# Bpod_Serial_Shield_r3.net
KiCad netlist of a schematic drawn in EAGLE
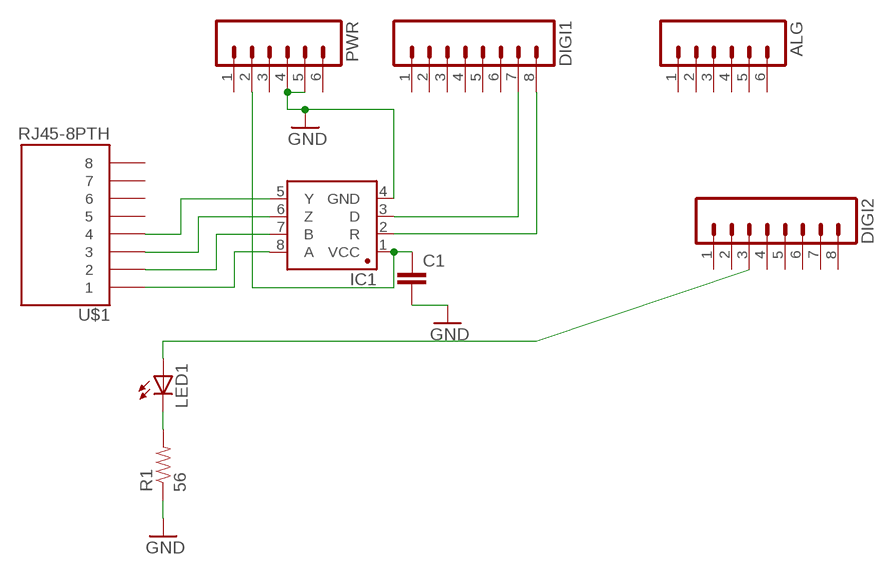
[diagram p0: schematic, sheet 1]

(export (version "E")
  (design (tool "Eeschema 10.0.6"))
  (components
    (comp (ref "ALG")
      (value "M06LONGPADS")
      (footprint "eagle-import:1X06_LONGPADS")
      (libsource (lib "eagle-import") (part "M06LONGPADS"))
    )
    (comp (ref "C1")
      (value "CAP1206")
      (footprint "eagle-import:1206")
      (libsource (lib "eagle-import") (part "CAP1206"))
    )
    (comp (ref "DIGI1")
      (value "M08LONGPADS")
      (footprint "eagle-import:1X08_LONGPADS")
      (libsource (lib "eagle-import") (part "M08LONGPADS"))
    )
    (comp (ref "DIGI2")
      (value "M08LONGPADS")
      (footprint "eagle-import:1X08_LONGPADS")
      (libsource (lib "eagle-import") (part "M08LONGPADS"))
    )
    (comp (ref "IC1")
      (value "SN65HVD31DR")
      (footprint "eagle-import:SO08")
      (libsource (lib "eagle-import") (part "SN65HVD31DR"))
    )
    (comp (ref "LED1")
      (value "LEDCHIPLED_1206")
      (footprint "eagle-import:CHIPLED_1206")
      (libsource (lib "eagle-import") (part "LEDCHIPLED_1206"))
    )
    (comp (ref "PWR")
      (value "M06LONGPADS")
      (footprint "eagle-import:1X06_LONGPADS")
      (libsource (lib "eagle-import") (part "M06LONGPADS"))
    )
    (comp (ref "R1")
      (value "56")
      (footprint "eagle-import:1206")
      (libsource (lib "eagle-import") (part "RESISTOR1206"))
    )
    (comp (ref "U$1")
      (value "RJ45-8PTH")
      (footprint "eagle-import:RJ45-8")
      (libsource (lib "eagle-import") (part "RJ45-8PTH"))
    )
  )
  (nets
    (net (code "1") (name "GND") (class "Default")
      (node (ref "C1") (pin "2") (pinfunction "2_2") (pintype "passive"))
      (node (ref "IC1") (pin "4") (pinfunction "GND_4") (pintype "bidirectional"))
      (node (ref "PWR") (pin "4") (pinfunction "4_4") (pintype "passive"))
      (node (ref "PWR") (pin "5") (pinfunction "5_5") (pintype "passive"))
      (node (ref "R1") (pin "1") (pinfunction "1_1") (pintype "passive"))
    )
    (net (code "2") (name "Net-(DIGI2-Pad3)") (class "Default")
      (node (ref "DIGI2") (pin "3") (pinfunction "3_3") (pintype "passive"))
      (node (ref "LED1") (pin "A") (pinfunction "A_A") (pintype "passive"))
    )
    (net (code "3") (name "Net-(IC1-A)") (class "Default")
      (node (ref "IC1") (pin "8") (pinfunction "A_8") (pintype "bidirectional"))
      (node (ref "U$1") (pin "1") (pinfunction "1_1") (pintype "bidirectional"))
    )
    (net (code "4") (name "Net-(IC1-B)") (class "Default")
      (node (ref "IC1") (pin "7") (pinfunction "B_7") (pintype "bidirectional"))
      (node (ref "U$1") (pin "2") (pinfunction "2_2") (pintype "bidirectional"))
    )
    (net (code "5") (name "Net-(IC1-D)") (class "Default")
      (node (ref "DIGI1") (pin "7") (pinfunction "7_7") (pintype "passive"))
      (node (ref "IC1") (pin "3") (pinfunction "D_3") (pintype "bidirectional"))
    )
    (net (code "6") (name "Net-(IC1-R)") (class "Default")
      (node (ref "DIGI1") (pin "8") (pinfunction "8_8") (pintype "passive"))
      (node (ref "IC1") (pin "2") (pinfunction "R_2") (pintype "bidirectional"))
    )
    (net (code "7") (name "Net-(IC1-VCC)") (class "Default")
      (node (ref "C1") (pin "1") (pinfunction "1_1") (pintype "passive"))
      (node (ref "IC1") (pin "1") (pinfunction "VCC_1") (pintype "bidirectional"))
      (node (ref "PWR") (pin "2") (pinfunction "2_2") (pintype "passive"))
    )
    (net (code "8") (name "Net-(IC1-Y)") (class "Default")
      (node (ref "IC1") (pin "5") (pinfunction "Y_5") (pintype "bidirectional"))
      (node (ref "U$1") (pin "4") (pinfunction "4_4") (pintype "bidirectional"))
    )
    (net (code "9") (name "Net-(IC1-Z)") (class "Default")
      (node (ref "IC1") (pin "6") (pinfunction "Z_6") (pintype "bidirectional"))
      (node (ref "U$1") (pin "3") (pinfunction "3_3") (pintype "bidirectional"))
    )
    (net (code "10") (name "Net-(LED1-PadC)") (class "Default")
      (node (ref "LED1") (pin "C") (pinfunction "C_C") (pintype "passive"))
      (node (ref "R1") (pin "2") (pinfunction "2_2") (pintype "passive"))
    )
    (net (code "11") (name "unconnected-(ALG-Pad1)") (class "Default")
      (node (ref "ALG") (pin "1") (pinfunction "1_1") (pintype "passive"))
    )
    (net (code "12") (name "unconnected-(ALG-Pad2)") (class "Default")
      (node (ref "ALG") (pin "2") (pinfunction "2_2") (pintype "passive"))
    )
    (net (code "13") (name "unconnected-(ALG-Pad3)") (class "Default")
      (node (ref "ALG") (pin "3") (pinfunction "3_3") (pintype "passive"))
    )
    (net (code "14") (name "unconnected-(ALG-Pad4)") (class "Default")
      (node (ref "ALG") (pin "4") (pinfunction "4_4") (pintype "passive"))
    )
    (net (code "15") (name "unconnected-(ALG-Pad5)") (class "Default")
      (node (ref "ALG") (pin "5") (pinfunction "5_5") (pintype "passive"))
    )
    (net (code "16") (name "unconnected-(ALG-Pad6)") (class "Default")
      (node (ref "ALG") (pin "6") (pinfunction "6_6") (pintype "passive"))
    )
    (net (code "17") (name "unconnected-(DIGI1-Pad1)") (class "Default")
      (node (ref "DIGI1") (pin "1") (pinfunction "1_1") (pintype "passive"))
    )
    (net (code "18") (name "unconnected-(DIGI1-Pad2)") (class "Default")
      (node (ref "DIGI1") (pin "2") (pinfunction "2_2") (pintype "passive"))
    )
    (net (code "19") (name "unconnected-(DIGI1-Pad3)") (class "Default")
      (node (ref "DIGI1") (pin "3") (pinfunction "3_3") (pintype "passive"))
    )
    (net (code "20") (name "unconnected-(DIGI1-Pad4)") (class "Default")
      (node (ref "DIGI1") (pin "4") (pinfunction "4_4") (pintype "passive"))
    )
    (net (code "21") (name "unconnected-(DIGI1-Pad5)") (class "Default")
      (node (ref "DIGI1") (pin "5") (pinfunction "5_5") (pintype "passive"))
    )
    (net (code "22") (name "unconnected-(DIGI1-Pad6)") (class "Default")
      (node (ref "DIGI1") (pin "6") (pinfunction "6_6") (pintype "passive"))
    )
    (net (code "23") (name "unconnected-(DIGI2-Pad1)") (class "Default")
      (node (ref "DIGI2") (pin "1") (pinfunction "1_1") (pintype "passive"))
    )
    (net (code "24") (name "unconnected-(DIGI2-Pad2)") (class "Default")
      (node (ref "DIGI2") (pin "2") (pinfunction "2_2") (pintype "passive"))
    )
    (net (code "25") (name "unconnected-(DIGI2-Pad4)") (class "Default")
      (node (ref "DIGI2") (pin "4") (pinfunction "4_4") (pintype "passive"))
    )
    (net (code "26") (name "unconnected-(DIGI2-Pad5)") (class "Default")
      (node (ref "DIGI2") (pin "5") (pinfunction "5_5") (pintype "passive"))
    )
    (net (code "27") (name "unconnected-(DIGI2-Pad6)") (class "Default")
      (node (ref "DIGI2") (pin "6") (pinfunction "6_6") (pintype "passive"))
    )
    (net (code "28") (name "unconnected-(DIGI2-Pad7)") (class "Default")
      (node (ref "DIGI2") (pin "7") (pinfunction "7_7") (pintype "passive"))
    )
    (net (code "29") (name "unconnected-(DIGI2-Pad8)") (class "Default")
      (node (ref "DIGI2") (pin "8") (pinfunction "8_8") (pintype "passive"))
    )
    (net (code "30") (name "unconnected-(PWR-Pad1)") (class "Default")
      (node (ref "PWR") (pin "1") (pinfunction "1_1") (pintype "passive"))
    )
    (net (code "31") (name "unconnected-(PWR-Pad3)") (class "Default")
      (node (ref "PWR") (pin "3") (pinfunction "3_3") (pintype "passive"))
    )
    (net (code "32") (name "unconnected-(PWR-Pad6)") (class "Default")
      (node (ref "PWR") (pin "6") (pinfunction "6_6") (pintype "passive"))
    )
    (net (code "33") (name "unconnected-(U$1-Pad5)") (class "Default")
      (node (ref "U$1") (pin "5") (pinfunction "5_5") (pintype "bidirectional"))
    )
    (net (code "34") (name "unconnected-(U$1-Pad6)") (class "Default")
      (node (ref "U$1") (pin "6") (pinfunction "6_6") (pintype "bidirectional"))
    )
    (net (code "35") (name "unconnected-(U$1-Pad7)") (class "Default")
      (node (ref "U$1") (pin "7") (pinfunction "7_7") (pintype "bidirectional"))
    )
    (net (code "36") (name "unconnected-(U$1-Pad8)") (class "Default")
      (node (ref "U$1") (pin "8") (pinfunction "8_8") (pintype "bidirectional"))
    )
  )
)
